# Wifi_Shield_v1_2.net
KiCad netlist of a schematic drawn in EAGLE
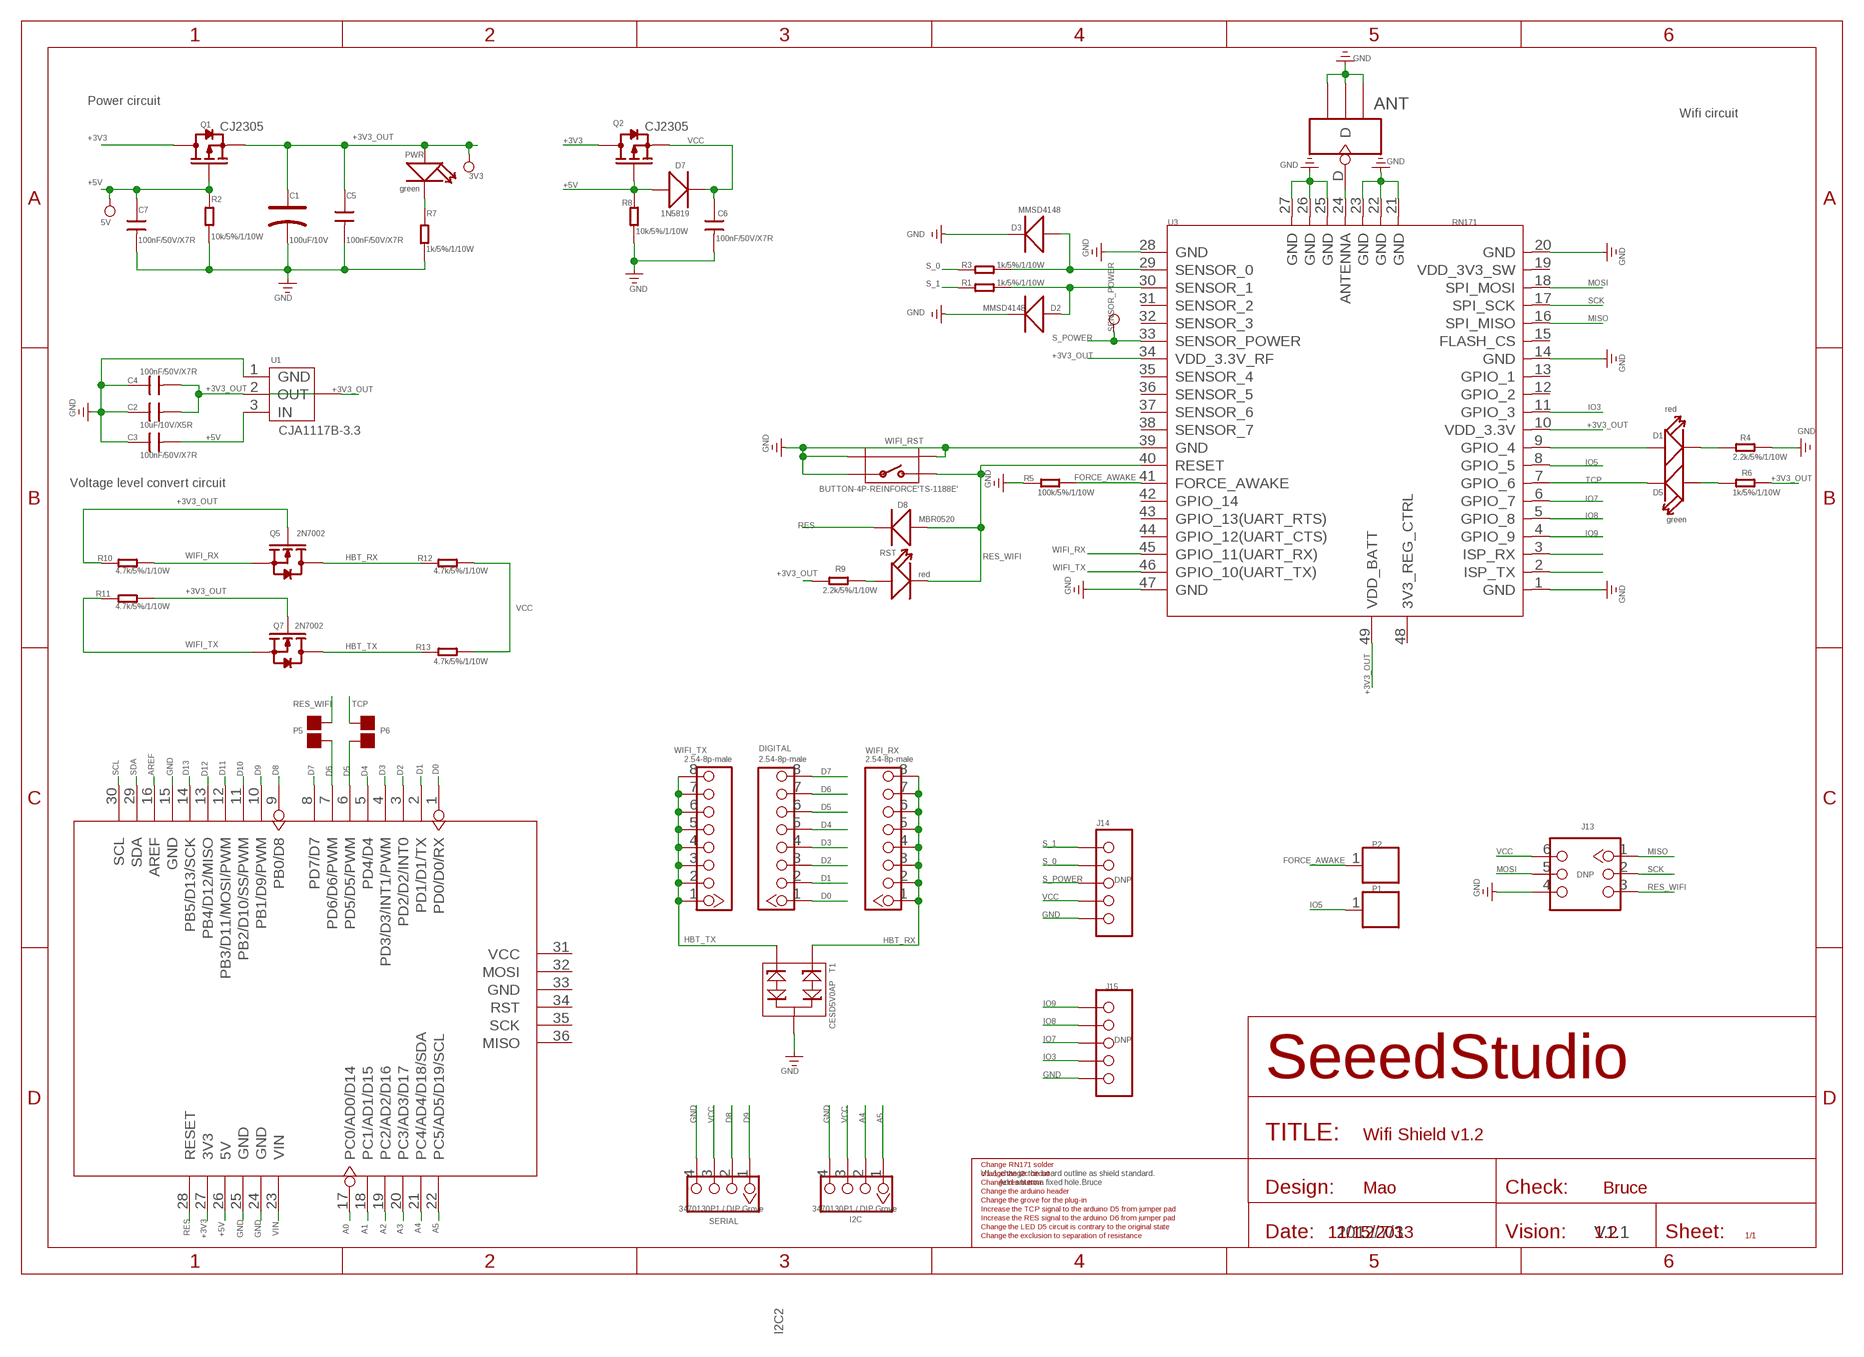
[diagram p0: schematic, sheet 1]

(export (version "E")
  (design (tool "Eeschema 10.0.6"))
  (components
    (comp (ref "3V3")
      (value "PAD-TEST-POINT-CIRCLE_SIZE_3030")
      (footprint "eagle-import:TP_3535")
      (libsource (lib "eagle-import") (part "PAD-TEST-POINT-CIRCLE_SIZE_3030"))
    )
    (comp (ref "5V")
      (value "PAD-TEST-POINT-CIRCLE_SIZE_3030")
      (footprint "eagle-import:TP_3535")
      (libsource (lib "eagle-import") (part "PAD-TEST-POINT-CIRCLE_SIZE_3030"))
    )
    (comp (ref "ANT1")
      (value "ANT")
      (footprint "eagle-import:4P-U-FL")
      (libsource (lib "eagle-import") (part "ANTENNA-U-FL"))
    )
    (comp (ref "C1")
      (value "100uF/10V")
      (footprint "eagle-import:AVX-B")
      (libsource (lib "eagle-import") (part "CAP-AVX-B"))
    )
    (comp (ref "C2")
      (value "10uF/10V/X5R")
      (footprint "eagle-import:0603")
      (libsource (lib "eagle-import") (part "C-0603"))
    )
    (comp (ref "C3")
      (value "100nF/50V/X7R")
      (footprint "eagle-import:0603")
      (libsource (lib "eagle-import") (part "C-0603"))
    )
    (comp (ref "C4")
      (value "100nF/50V/X7R")
      (footprint "eagle-import:0603")
      (libsource (lib "eagle-import") (part "C-0603"))
    )
    (comp (ref "C5")
      (value "100nF/50V/X7R")
      (footprint "eagle-import:0603")
      (libsource (lib "eagle-import") (part "C-0603"))
    )
    (comp (ref "C6")
      (value "100nF/50V/X7R")
      (footprint "eagle-import:0603")
      (libsource (lib "eagle-import") (part "C-0603"))
    )
    (comp (ref "C7")
      (value "100nF/50V/X7R")
      (footprint "eagle-import:0603")
      (libsource (lib "eagle-import") (part "C-0603"))
    )
    (comp (ref "D1")
      (value "red")
      (footprint "eagle-import:LED-0603")
      (libsource (lib "eagle-import") (part "LED'0603'"))
    )
    (comp (ref "D2")
      (value "MMSD4148")
      (footprint "eagle-import:SOD123-2.7X1.6")
      (libsource (lib "eagle-import") (part "D-MBR0520LT1"))
    )
    (comp (ref "D3")
      (value "MMSD4148")
      (footprint "eagle-import:SOD123-2.7X1.6")
      (libsource (lib "eagle-import") (part "D-MBR0520LT1"))
    )
    (comp (ref "D5")
      (value "green")
      (footprint "eagle-import:LED-0603")
      (libsource (lib "eagle-import") (part "LED'0603'"))
    )
    (comp (ref "D7")
      (value "1N5819")
      (footprint "eagle-import:D2010")
      (libsource (lib "eagle-import") (part "D-SMA"))
    )
    (comp (ref "D8")
      (value "MBR0520")
      (footprint "eagle-import:SOD123-2.7X1.6")
      (libsource (lib "eagle-import") (part "D-MBR0520LT1"))
    )
    (comp (ref "DIGITAL")
      (value "2.54-8p-male")
      (footprint "eagle-import:8P-2.54")
      (libsource (lib "eagle-import") (part "HEADER-8P-2.54"))
    )
    (comp (ref "I2C")
      (value "3470130P1 / DIP Grove")
      (footprint "eagle-import:4P-2.0")
      (libsource (lib "eagle-import") (part "TWIG-4P-2.0-2.0"))
    )
    (comp (ref "J13")
      (value "DNP")
      (footprint "eagle-import:2X3P-2.54")
      (libsource (lib "eagle-import") (part "HEADER-2X3P-2.54"))
    )
    (comp (ref "J14")
      (value "DNP")
      (footprint "eagle-import:5P-2.54")
      (libsource (lib "eagle-import") (part "HEADER-5P-2.54"))
    )
    (comp (ref "J15")
      (value "DNP")
      (footprint "eagle-import:5P-2.54")
      (libsource (lib "eagle-import") (part "HEADER-5P-2.54"))
    )
    (comp (ref "P1")
      (value "DNP")
      (footprint "eagle-import:1P-65_35MIL")
      (libsource (lib "eagle-import") (part "PAD'60/30'"))
    )
    (comp (ref "P2")
      (value "DNP")
      (footprint "eagle-import:1P-65_35MIL")
      (libsource (lib "eagle-import") (part "PAD'60/30'"))
    )
    (comp (ref "P5")
      (value "DNP")
      (footprint "eagle-import:2P-SMD-1.78X1.27")
      (libsource (lib "eagle-import") (part "PAD-JUMPER-2P"))
    )
    (comp (ref "P6")
      (value "DNP")
      (footprint "eagle-import:2P-SMD-1.78X1.27")
      (libsource (lib "eagle-import") (part "PAD-JUMPER-2P"))
    )
    (comp (ref "PWR")
      (value "green")
      (footprint "eagle-import:LED-0603")
      (libsource (lib "eagle-import") (part "LED'0603'"))
    )
    (comp (ref "Q1")
      (value "CJ2305")
      (footprint "eagle-import:SOT23")
      (libsource (lib "eagle-import") (part "MOSFET-P'SI2323CDS/SI2305DS{lt}BR{gt}'"))
    )
    (comp (ref "Q2")
      (value "CJ2305")
      (footprint "eagle-import:SOT23")
      (libsource (lib "eagle-import") (part "MOSFET-P'SI2323CDS/SI2305DS{lt}BR{gt}'"))
    )
    (comp (ref "Q5")
      (value "2N7002")
      (footprint "eagle-import:SOT23")
      (libsource (lib "eagle-import") (part "MOSFET-N'SOT23'"))
    )
    (comp (ref "Q7")
      (value "2N7002")
      (footprint "eagle-import:SOT23")
      (libsource (lib "eagle-import") (part "MOSFET-N'SOT23'"))
    )
    (comp (ref "R1")
      (value "1k/5%/1/10W")
      (footprint "eagle-import:0603")
      (libsource (lib "eagle-import") (part "R-0603"))
    )
    (comp (ref "R2")
      (value "10k/5%/1/10W")
      (footprint "eagle-import:0603")
      (libsource (lib "eagle-import") (part "R-0603"))
    )
    (comp (ref "R3")
      (value "1k/5%/1/10W")
      (footprint "eagle-import:0603")
      (libsource (lib "eagle-import") (part "R-0603"))
    )
    (comp (ref "R4")
      (value "2.2k/5%/1/10W")
      (footprint "eagle-import:0603")
      (libsource (lib "eagle-import") (part "R-0603"))
    )
    (comp (ref "R5")
      (value "100k/5%/1/10W")
      (footprint "eagle-import:0603")
      (libsource (lib "eagle-import") (part "R-0603"))
    )
    (comp (ref "R6")
      (value "1k/5%/1/10W")
      (footprint "eagle-import:0603")
      (libsource (lib "eagle-import") (part "R-0603"))
    )
    (comp (ref "R7")
      (value "1k/5%/1/10W")
      (footprint "eagle-import:0603")
      (libsource (lib "eagle-import") (part "R-0603"))
    )
    (comp (ref "R8")
      (value "10k/5%/1/10W")
      (footprint "eagle-import:0603")
      (libsource (lib "eagle-import") (part "R-0603"))
    )
    (comp (ref "R9")
      (value "2.2k/5%/1/10W")
      (footprint "eagle-import:0603")
      (libsource (lib "eagle-import") (part "R-0603"))
    )
    (comp (ref "R10")
      (value "4.7k/5%/1/10W")
      (footprint "eagle-import:0603")
      (libsource (lib "eagle-import") (part "R-0603"))
    )
    (comp (ref "R11")
      (value "4.7k/5%/1/10W")
      (footprint "eagle-import:0603")
      (libsource (lib "eagle-import") (part "R-0603"))
    )
    (comp (ref "R12")
      (value "4.7k/5%/1/10W")
      (footprint "eagle-import:0603")
      (libsource (lib "eagle-import") (part "R-0603"))
    )
    (comp (ref "R13")
      (value "4.7k/5%/1/10W")
      (footprint "eagle-import:0603")
      (libsource (lib "eagle-import") (part "R-0603"))
    )
    (comp (ref "RST")
      (value "red")
      (footprint "eagle-import:LED-0603")
      (libsource (lib "eagle-import") (part "LED'0603'"))
    )
    (comp (ref "SENSOR_POWER")
      (value "PAD-TEST-POINT-CIRCLE_SIZE_3030")
      (footprint "eagle-import:TP_3535")
      (libsource (lib "eagle-import") (part "PAD-TEST-POINT-CIRCLE_SIZE_3030"))
    )
    (comp (ref "SERIAL")
      (value "3470130P1 / DIP Grove")
      (footprint "eagle-import:4P-2.0")
      (libsource (lib "eagle-import") (part "TWIG-4P-2.0-2.0"))
    )
    (comp (ref "T1")
      (value "CESD5V0AP")
      (footprint "eagle-import:SOT23")
      (libsource (lib "eagle-import") (part "D-ESD-PESDXL2BT"))
    )
    (comp (ref "U1")
      (value "CJA1117B-3.3")
      (footprint "eagle-import:SOT89")
      (libsource (lib "eagle-import") (part "LD1117SOT89"))
    )
    (comp (ref "U2")
      (value "ARDUINO'W/O-SILK'")
      (footprint "eagle-import:ARDUINO-W_O-SILK")
      (libsource (lib "eagle-import") (part "ARDUINO'W/O-SILK'"))
    )
    (comp (ref "U3")
      (value "RN171")
      (footprint "eagle-import:49P-1.27-26.67X17.78")
      (libsource (lib "eagle-import") (part "WIFI-RN-171"))
    )
    (comp (ref "WIFI_RST")
      (value "BUTTON-4P-REINFORCE'TS-1188E'")
      (footprint "eagle-import:4P-SMD-7X3.5X3.5H")
      (libsource (lib "eagle-import") (part "BUTTON-4P-REINFORCE'TS-1188E'"))
    )
    (comp (ref "WIFI_RX")
      (value "2.54-8p-male")
      (footprint "eagle-import:8P-2.54")
      (libsource (lib "eagle-import") (part "HEADER-8P-2.54"))
    )
    (comp (ref "WIFI_TX")
      (value "2.54-8p-male")
      (footprint "eagle-import:8P-2.54")
      (libsource (lib "eagle-import") (part "HEADER-8P-2.54"))
    )
  )
  (nets
    (net (code "1") (name "/+3V3") (class "Default")
      (node (ref "Q1") (pin "3") (pinfunction "D_3") (pintype "passive"))
      (node (ref "Q2") (pin "3") (pinfunction "D_3") (pintype "passive"))
      (node (ref "U2") (pin "27") (pinfunction "3V3_27") (pintype "bidirectional"))
    )
    (net (code "2") (name "/+3V3_OUT") (class "Default")
      (node (ref "3V3") (pin "T") (pinfunction "T_T") (pintype "bidirectional"))
      (node (ref "C1") (pin "+") (pinfunction "+_+") (pintype "passive"))
      (node (ref "C2") (pin "2") (pinfunction "2_2") (pintype "passive"))
      (node (ref "C4") (pin "2") (pinfunction "2_2") (pintype "passive"))
      (node (ref "C5") (pin "1") (pinfunction "1_1") (pintype "passive"))
      (node (ref "PWR") (pin "+") (pinfunction "+_+") (pintype "passive"))
      (node (ref "Q1") (pin "2") (pinfunction "S_2") (pintype "passive"))
      (node (ref "Q5") (pin "1") (pinfunction "G_1") (pintype "passive"))
      (node (ref "Q7") (pin "1") (pinfunction "G_1") (pintype "passive"))
      (node (ref "R10") (pin "2") (pinfunction "2_2") (pintype "passive"))
      (node (ref "R11") (pin "1") (pinfunction "1_1") (pintype "passive"))
      (node (ref "R6") (pin "1") (pinfunction "1_1") (pintype "passive"))
      (node (ref "R9") (pin "2") (pinfunction "2_2") (pintype "passive"))
      (node (ref "U1") (pin "2") (pinfunction "OUT_2") (pintype "bidirectional"))
      (node (ref "U1") (pin "4") (pinfunction "TAB_4") (pintype "bidirectional"))
      (node (ref "U3") (pin "10") (pinfunction "VDD_3.3V_10") (pintype "power_in"))
      (node (ref "U3") (pin "34") (pinfunction "VDD_3.3V_RF_34") (pintype "power_in"))
      (node (ref "U3") (pin "49") (pinfunction "VDD_BATT_49") (pintype "bidirectional"))
    )
    (net (code "3") (name "/+5V") (class "Default")
      (node (ref "5V") (pin "T") (pinfunction "T_T") (pintype "bidirectional"))
      (node (ref "C3") (pin "2") (pinfunction "2_2") (pintype "passive"))
      (node (ref "C7") (pin "1") (pinfunction "1_1") (pintype "passive"))
      (node (ref "D7") (pin "+") (pinfunction "+_+") (pintype "passive"))
      (node (ref "Q1") (pin "1") (pinfunction "G_1") (pintype "passive"))
      (node (ref "Q2") (pin "1") (pinfunction "G_1") (pintype "passive"))
      (node (ref "R2") (pin "1") (pinfunction "1_1") (pintype "passive"))
      (node (ref "R8") (pin "1") (pinfunction "1_1") (pintype "passive"))
      (node (ref "U1") (pin "3") (pinfunction "IN_3") (pintype "bidirectional"))
      (node (ref "U2") (pin "26") (pinfunction "5V_26") (pintype "bidirectional"))
    )
    (net (code "4") (name "/A0") (class "Default")
      (node (ref "U2") (pin "17") (pinfunction "PC0/AD0/D14_17") (pintype "bidirectional"))
    )
    (net (code "5") (name "/A1") (class "Default")
      (node (ref "U2") (pin "18") (pinfunction "PC1/AD1/D15_18") (pintype "bidirectional"))
    )
    (net (code "6") (name "/A2") (class "Default")
      (node (ref "U2") (pin "19") (pinfunction "PC2/AD2/D16_19") (pintype "bidirectional"))
    )
    (net (code "7") (name "/A3") (class "Default")
      (node (ref "U2") (pin "20") (pinfunction "PC3/AD3/D17_20") (pintype "bidirectional"))
    )
    (net (code "8") (name "/A4") (class "Default")
      (node (ref "I2C") (pin "2") (pinfunction "2_2") (pintype "bidirectional"))
      (node (ref "U2") (pin "21") (pinfunction "PC4/AD4/D18/SDA_21") (pintype "bidirectional"))
    )
    (net (code "9") (name "/A5") (class "Default")
      (node (ref "I2C") (pin "1") (pinfunction "1_1") (pintype "bidirectional"))
      (node (ref "U2") (pin "22") (pinfunction "PC5/AD5/D19/SCL_22") (pintype "bidirectional"))
    )
    (net (code "10") (name "/AREF") (class "Default")
      (node (ref "U2") (pin "16") (pinfunction "AREF_16") (pintype "bidirectional"))
    )
    (net (code "11") (name "/D0") (class "Default")
      (node (ref "DIGITAL") (pin "1") (pinfunction "1_1") (pintype "bidirectional"))
      (node (ref "U2") (pin "1") (pinfunction "PD0/D0/RX_1") (pintype "bidirectional"))
    )
    (net (code "12") (name "/D1") (class "Default")
      (node (ref "DIGITAL") (pin "2") (pinfunction "2_2") (pintype "bidirectional"))
      (node (ref "U2") (pin "2") (pinfunction "PD1/D1/TX_2") (pintype "bidirectional"))
    )
    (net (code "13") (name "/D2") (class "Default")
      (node (ref "DIGITAL") (pin "3") (pinfunction "3_3") (pintype "bidirectional"))
      (node (ref "U2") (pin "3") (pinfunction "PD2/D2/INT0_3") (pintype "bidirectional"))
    )
    (net (code "14") (name "/D3") (class "Default")
      (node (ref "DIGITAL") (pin "4") (pinfunction "4_4") (pintype "bidirectional"))
      (node (ref "U2") (pin "4") (pinfunction "PD3/D3/INT1/PWM_4") (pintype "bidirectional"))
    )
    (net (code "15") (name "/D4") (class "Default")
      (node (ref "DIGITAL") (pin "5") (pinfunction "5_5") (pintype "bidirectional"))
      (node (ref "U2") (pin "5") (pinfunction "PD4/D4_5") (pintype "bidirectional"))
    )
    (net (code "16") (name "/D5") (class "Default")
      (node (ref "DIGITAL") (pin "6") (pinfunction "6_6") (pintype "bidirectional"))
      (node (ref "P6") (pin "2") (pinfunction "2_2") (pintype "bidirectional"))
      (node (ref "U2") (pin "6") (pinfunction "PD5/D5/PWM_6") (pintype "bidirectional"))
    )
    (net (code "17") (name "/D6") (class "Default")
      (node (ref "DIGITAL") (pin "7") (pinfunction "7_7") (pintype "bidirectional"))
      (node (ref "P5") (pin "1") (pinfunction "1_1") (pintype "bidirectional"))
      (node (ref "U2") (pin "7") (pinfunction "PD6/D6/PWM_7") (pintype "bidirectional"))
    )
    (net (code "18") (name "/D7") (class "Default")
      (node (ref "DIGITAL") (pin "8") (pinfunction "8_8") (pintype "bidirectional"))
      (node (ref "U2") (pin "8") (pinfunction "PD7/D7_8") (pintype "bidirectional"))
    )
    (net (code "19") (name "/D8") (class "Default")
      (node (ref "SERIAL") (pin "2") (pinfunction "2_2") (pintype "bidirectional"))
      (node (ref "U2") (pin "9") (pinfunction "PB0/D8_9") (pintype "bidirectional"))
    )
    (net (code "20") (name "/D9") (class "Default")
      (node (ref "SERIAL") (pin "1") (pinfunction "1_1") (pintype "bidirectional"))
      (node (ref "U2") (pin "10") (pinfunction "PB1/D9/PWM_10") (pintype "bidirectional"))
    )
    (net (code "21") (name "/D10") (class "Default")
      (node (ref "U2") (pin "11") (pinfunction "PB2/D10/SS/PWM_11") (pintype "bidirectional"))
    )
    (net (code "22") (name "/D11") (class "Default")
      (node (ref "U2") (pin "12") (pinfunction "PB3/D11/MOSI/PWM_12") (pintype "bidirectional"))
    )
    (net (code "23") (name "/D12") (class "Default")
      (node (ref "U2") (pin "13") (pinfunction "PB4/D12/MISO_13") (pintype "bidirectional"))
    )
    (net (code "24") (name "/D13") (class "Default")
      (node (ref "U2") (pin "14") (pinfunction "PB5/D13/SCK_14") (pintype "bidirectional"))
    )
    (net (code "25") (name "/FORCE_AWAKE") (class "Default")
      (node (ref "P2") (pin "1") (pinfunction "P$1_1") (pintype "bidirectional"))
      (node (ref "R5") (pin "1") (pinfunction "1_1") (pintype "passive"))
      (node (ref "U3") (pin "41") (pinfunction "FORCE_AWAKE_41") (pintype "bidirectional"))
    )
    (net (code "26") (name "/HBT_RX") (class "Default")
      (node (ref "Q5") (pin "3") (pinfunction "D_3") (pintype "passive"))
      (node (ref "R12") (pin "2") (pinfunction "2_2") (pintype "passive"))
      (node (ref "T1") (pin "1") (pinfunction "1_1") (pintype "power_in"))
      (node (ref "WIFI_RX") (pin "1") (pinfunction "1_1") (pintype "bidirectional"))
      (node (ref "WIFI_RX") (pin "2") (pinfunction "2_2") (pintype "bidirectional"))
      (node (ref "WIFI_RX") (pin "3") (pinfunction "3_3") (pintype "bidirectional"))
      (node (ref "WIFI_RX") (pin "4") (pinfunction "4_4") (pintype "bidirectional"))
      (node (ref "WIFI_RX") (pin "5") (pinfunction "5_5") (pintype "bidirectional"))
      (node (ref "WIFI_RX") (pin "6") (pinfunction "6_6") (pintype "bidirectional"))
      (node (ref "WIFI_RX") (pin "7") (pinfunction "7_7") (pintype "bidirectional"))
      (node (ref "WIFI_RX") (pin "8") (pinfunction "8_8") (pintype "bidirectional"))
    )
    (net (code "27") (name "/HBT_TX") (class "Default")
      (node (ref "Q7") (pin "3") (pinfunction "D_3") (pintype "passive"))
      (node (ref "R13") (pin "2") (pinfunction "2_2") (pintype "passive"))
      (node (ref "T1") (pin "2") (pinfunction "2_2") (pintype "power_in"))
      (node (ref "WIFI_TX") (pin "1") (pinfunction "1_1") (pintype "bidirectional"))
      (node (ref "WIFI_TX") (pin "2") (pinfunction "2_2") (pintype "bidirectional"))
      (node (ref "WIFI_TX") (pin "3") (pinfunction "3_3") (pintype "bidirectional"))
      (node (ref "WIFI_TX") (pin "4") (pinfunction "4_4") (pintype "bidirectional"))
      (node (ref "WIFI_TX") (pin "5") (pinfunction "5_5") (pintype "bidirectional"))
      (node (ref "WIFI_TX") (pin "6") (pinfunction "6_6") (pintype "bidirectional"))
      (node (ref "WIFI_TX") (pin "7") (pinfunction "7_7") (pintype "bidirectional"))
      (node (ref "WIFI_TX") (pin "8") (pinfunction "8_8") (pintype "bidirectional"))
    )
    (net (code "28") (name "/IO3") (class "Default")
      (node (ref "J15") (pin "4") (pinfunction "4_4") (pintype "bidirectional"))
      (node (ref "U3") (pin "11") (pinfunction "GPIO_3_11") (pintype "bidirectional"))
    )
    (net (code "29") (name "/IO5") (class "Default")
      (node (ref "P1") (pin "1") (pinfunction "P$1_1") (pintype "bidirectional"))
      (node (ref "U3") (pin "8") (pinfunction "GPIO_5_8") (pintype "bidirectional"))
    )
    (net (code "30") (name "/IO7") (class "Default")
      (node (ref "J15") (pin "3") (pinfunction "3_3") (pintype "bidirectional"))
      (node (ref "U3") (pin "6") (pinfunction "GPIO_7_6") (pintype "bidirectional"))
    )
    (net (code "31") (name "/IO8") (class "Default")
      (node (ref "J15") (pin "2") (pinfunction "2_2") (pintype "bidirectional"))
      (node (ref "U3") (pin "5") (pinfunction "GPIO_8_5") (pintype "bidirectional"))
    )
    (net (code "32") (name "/IO9") (class "Default")
      (node (ref "J15") (pin "1") (pinfunction "1_1") (pintype "bidirectional"))
      (node (ref "U3") (pin "4") (pinfunction "GPIO_9_4") (pintype "bidirectional"))
    )
    (net (code "33") (name "/MISO") (class "Default")
      (node (ref "J13") (pin "1") (pinfunction "1_1") (pintype "bidirectional"))
      (node (ref "U3") (pin "16") (pinfunction "SPI_MISO_16") (pintype "bidirectional"))
    )
    (net (code "34") (name "/MOSI") (class "Default")
      (node (ref "J13") (pin "5") (pinfunction "5_5") (pintype "bidirectional"))
      (node (ref "U3") (pin "18") (pinfunction "SPI_MOSI_18") (pintype "bidirectional"))
    )
    (net (code "35") (name "/RES") (class "Default")
      (node (ref "D8") (pin "1") (pinfunction "-_1") (pintype "passive"))
      (node (ref "U2") (pin "28") (pinfunction "RESET_28") (pintype "bidirectional"))
    )
    (net (code "36") (name "/RES_WIFI") (class "Default")
      (node (ref "D8") (pin "2") (pinfunction "+_2") (pintype "passive"))
      (node (ref "J13") (pin "3") (pinfunction "3_3") (pintype "bidirectional"))
      (node (ref "P5") (pin "2") (pinfunction "2_2") (pintype "bidirectional"))
      (node (ref "RST") (pin "-") (pinfunction "-_-") (pintype "passive"))
      (node (ref "U3") (pin "40") (pinfunction "RESET_40") (pintype "input"))
      (node (ref "WIFI_RST") (pin "2") (pinfunction "2_2") (pintype "bidirectional"))
    )
    (net (code "37") (name "/SCK") (class "Default")
      (node (ref "J13") (pin "2") (pinfunction "2_2") (pintype "bidirectional"))
      (node (ref "U3") (pin "17") (pinfunction "SPI_SCK_17") (pintype "bidirectional"))
    )
    (net (code "38") (name "/SCL") (class "Default")
      (node (ref "U2") (pin "30") (pinfunction "SCL_30") (pintype "bidirectional"))
    )
    (net (code "39") (name "/SDA") (class "Default")
      (node (ref "U2") (pin "29") (pinfunction "SDA_29") (pintype "bidirectional"))
    )
    (net (code "40") (name "/S_0") (class "Default")
      (node (ref "J14") (pin "2") (pinfunction "2_2") (pintype "bidirectional"))
      (node (ref "R3") (pin "2") (pinfunction "2_2") (pintype "passive"))
    )
    (net (code "41") (name "/S_1") (class "Default")
      (node (ref "J14") (pin "1") (pinfunction "1_1") (pintype "bidirectional"))
      (node (ref "R1") (pin "2") (pinfunction "2_2") (pintype "passive"))
    )
    (net (code "42") (name "/S_POWER") (class "Default")
      (node (ref "J14") (pin "3") (pinfunction "3_3") (pintype "bidirectional"))
      (node (ref "SENSOR_POWER") (pin "T") (pinfunction "T_T") (pintype "bidirectional"))
      (node (ref "U3") (pin "33") (pinfunction "SENSOR_POWER_33") (pintype "output"))
    )
    (net (code "43") (name "/TCP") (class "Default")
      (node (ref "D5") (pin "-") (pinfunction "-_-") (pintype "passive"))
      (node (ref "P6") (pin "1") (pinfunction "1_1") (pintype "bidirectional"))
      (node (ref "U3") (pin "7") (pinfunction "GPIO_6_7") (pintype "bidirectional"))
    )
    (net (code "44") (name "/VCC") (class "Default")
      (node (ref "C6") (pin "1") (pinfunction "1_1") (pintype "passive"))
      (node (ref "D7") (pin "-") (pinfunction "-_-") (pintype "passive"))
      (node (ref "I2C") (pin "3") (pinfunction "3_3") (pintype "bidirectional"))
      (node (ref "J13") (pin "6") (pinfunction "6_6") (pintype "bidirectional"))
      (node (ref "J14") (pin "4") (pinfunction "4_4") (pintype "bidirectional"))
      (node (ref "Q2") (pin "2") (pinfunction "S_2") (pintype "passive"))
      (node (ref "R12") (pin "1") (pinfunction "1_1") (pintype "passive"))
      (node (ref "R13") (pin "1") (pinfunction "1_1") (pintype "passive"))
      (node (ref "SERIAL") (pin "3") (pinfunction "3_3") (pintype "bidirectional"))
    )
    (net (code "45") (name "/VIN") (class "Default")
      (node (ref "U2") (pin "23") (pinfunction "VIN_23") (pintype "bidirectional"))
    )
    (net (code "46") (name "/WIFI_RX") (class "Default")
      (node (ref "Q5") (pin "2") (pinfunction "S_2") (pintype "passive"))
      (node (ref "R10") (pin "1") (pinfunction "1_1") (pintype "passive"))
      (node (ref "U3") (pin "45") (pinfunction "GPIO_11(UART_RX)_45") (pintype "bidirectional"))
    )
    (net (code "47") (name "/WIFI_TX") (class "Default")
      (node (ref "Q7") (pin "2") (pinfunction "S_2") (pintype "passive"))
      (node (ref "R11") (pin "2") (pinfunction "2_2") (pintype "passive"))
      (node (ref "U3") (pin "46") (pinfunction "GPIO_10(UART_TX)_46") (pintype "bidirectional"))
    )
    (net (code "48") (name "GND") (class "Default")
      (node (ref "ANT1") (pin "GND1") (pinfunction "GND1_GND1") (pintype "bidirectional"))
      (node (ref "ANT1") (pin "GND2") (pinfunction "GND2_GND2") (pintype "bidirectional"))
      (node (ref "ANT1") (pin "GND3") (pinfunction "GND3_GND3") (pintype "bidirectional"))
      (node (ref "C1") (pin "-") (pinfunction "-_-") (pintype "passive"))
      (node (ref "C2") (pin "1") (pinfunction "1_1") (pintype "passive"))
      (node (ref "C3") (pin "1") (pinfunction "1_1") (pintype "passive"))
      (node (ref "C4") (pin "1") (pinfunction "1_1") (pintype "passive"))
      (node (ref "C5") (pin "2") (pinfunction "2_2") (pintype "passive"))
      (node (ref "C6") (pin "2") (pinfunction "2_2") (pintype "passive"))
      (node (ref "C7") (pin "2") (pinfunction "2_2") (pintype "passive"))
      (node (ref "D2") (pin "1") (pinfunction "-_1") (pintype "passive"))
      (node (ref "D3") (pin "1") (pinfunction "-_1") (pintype "passive"))
      (node (ref "I2C") (pin "4") (pinfunction "4_4") (pintype "bidirectional"))
      (node (ref "J13") (pin "4") (pinfunction "4_4") (pintype "bidirectional"))
      (node (ref "J14") (pin "5") (pinfunction "5_5") (pintype "bidirectional"))
      (node (ref "J15") (pin "5") (pinfunction "5_5") (pintype "bidirectional"))
      (node (ref "R2") (pin "2") (pinfunction "2_2") (pintype "passive"))
      (node (ref "R4") (pin "1") (pinfunction "1_1") (pintype "passive"))
      (node (ref "R5") (pin "2") (pinfunction "2_2") (pintype "passive"))
      (node (ref "R7") (pin "1") (pinfunction "1_1") (pintype "passive"))
      (node (ref "R8") (pin "2") (pinfunction "2_2") (pintype "passive"))
      (node (ref "SERIAL") (pin "4") (pinfunction "4_4") (pintype "bidirectional"))
      (node (ref "T1") (pin "3") (pinfunction "3_3") (pintype "bidirectional"))
      (node (ref "U1") (pin "1") (pinfunction "GND_1") (pintype "bidirectional"))
      (node (ref "U2") (pin "15") (pinfunction "GND_15") (pintype "bidirectional"))
      (node (ref "U2") (pin "24") (pinfunction "GND_24") (pintype "bidirectional"))
      (node (ref "U2") (pin "25") (pinfunction "GND_25") (pintype "bidirectional"))
      (node (ref "U3") (pin "1") (pinfunction "GND_1") (pintype "power_in"))
      (node (ref "U3") (pin "14") (pinfunction "GND_14") (pintype "power_in"))
      (node (ref "U3") (pin "20") (pinfunction "GND_20") (pintype "power_in"))
      (node (ref "U3") (pin "21") (pinfunction "GND_21") (pintype "power_in"))
      (node (ref "U3") (pin "22") (pinfunction "GND_22") (pintype "power_in"))
      (node (ref "U3") (pin "23") (pinfunction "GND_23") (pintype "power_in"))
      (node (ref "U3") (pin "25") (pinfunction "GND_25") (pintype "power_in"))
      (node (ref "U3") (pin "26") (pinfunction "GND_26") (pintype "power_in"))
      (node (ref "U3") (pin "27") (pinfunction "GND_27") (pintype "power_in"))
      (node (ref "U3") (pin "28") (pinfunction "GND_28") (pintype "power_in"))
      (node (ref "U3") (pin "39") (pinfunction "GND_39") (pintype "power_in"))
      (node (ref "U3") (pin "47") (pinfunction "GND_47") (pintype "power_in"))
      (node (ref "WIFI_RST") (pin "1") (pinfunction "1_1") (pintype "bidirectional"))
      (node (ref "WIFI_RST") (pin "S1") (pinfunction "S1_S1") (pintype "bidirectional"))
      (node (ref "WIFI_RST") (pin "S2") (pinfunction "S2_S2") (pintype "bidirectional"))
    )
    (net (code "49") (name "Net-(D1-Pad-)") (class "Default")
      (node (ref "D1") (pin "-") (pinfunction "-_-") (pintype "passive"))
      (node (ref "R4") (pin "2") (pinfunction "2_2") (pintype "passive"))
    )
    (net (code "50") (name "Net-(D2-+)") (class "Default")
      (node (ref "D2") (pin "2") (pinfunction "+_2") (pintype "passive"))
      (node (ref "R1") (pin "1") (pinfunction "1_1") (pintype "passive"))
      (node (ref "U3") (pin "30") (pinfunction "SENSOR_1_30") (pintype "input"))
    )
    (net (code "51") (name "Net-(D3-+)") (class "Default")
      (node (ref "D3") (pin "2") (pinfunction "+_2") (pintype "passive"))
      (node (ref "R3") (pin "1") (pinfunction "1_1") (pintype "passive"))
      (node (ref "U3") (pin "29") (pinfunction "SENSOR_0_29") (pintype "input"))
    )
    (net (code "52") (name "Net-(D5-Pad+)") (class "Default")
      (node (ref "D5") (pin "+") (pinfunction "+_+") (pintype "passive"))
      (node (ref "R6") (pin "2") (pinfunction "2_2") (pintype "passive"))
    )
    (net (code "53") (name "Net-(PWR-Pad-)") (class "Default")
      (node (ref "PWR") (pin "-") (pinfunction "-_-") (pintype "passive"))
      (node (ref "R7") (pin "2") (pinfunction "2_2") (pintype "passive"))
    )
    (net (code "54") (name "Net-(R9-Pad1)") (class "Default")
      (node (ref "R9") (pin "1") (pinfunction "1_1") (pintype "passive"))
      (node (ref "RST") (pin "+") (pinfunction "+_+") (pintype "passive"))
    )
    (net (code "55") (name "Net-(U3-ANTENNA)") (class "Default")
      (node (ref "ANT1") (pin "D") (pinfunction "D_D") (pintype "bidirectional"))
      (node (ref "U3") (pin "24") (pinfunction "ANTENNA_24") (pintype "bidirectional"))
    )
    (net (code "56") (name "Net-(U3-GPIO_4)") (class "Default")
      (node (ref "D1") (pin "+") (pinfunction "+_+") (pintype "passive"))
      (node (ref "U3") (pin "9") (pinfunction "GPIO_4_9") (pintype "bidirectional"))
    )
    (net (code "57") (name "unconnected-(U2-GND-Pad33)") (class "Default")
      (node (ref "U2") (pin "33") (pinfunction "GND_33") (pintype "bidirectional"))
    )
    (net (code "58") (name "unconnected-(U2-MISO-Pad36)") (class "Default")
      (node (ref "U2") (pin "36") (pinfunction "MISO_36") (pintype "bidirectional"))
    )
    (net (code "59") (name "unconnected-(U2-MOSI-Pad32)") (class "Default")
      (node (ref "U2") (pin "32") (pinfunction "MOSI_32") (pintype "bidirectional"))
    )
    (net (code "60") (name "unconnected-(U2-RST-Pad34)") (class "Default")
      (node (ref "U2") (pin "34") (pinfunction "RST_34") (pintype "bidirectional"))
    )
    (net (code "61") (name "unconnected-(U2-SCK-Pad35)") (class "Default")
      (node (ref "U2") (pin "35") (pinfunction "SCK_35") (pintype "bidirectional"))
    )
    (net (code "62") (name "unconnected-(U2-VCC-Pad31)") (class "Default")
      (node (ref "U2") (pin "31") (pinfunction "VCC_31") (pintype "bidirectional"))
    )
    (net (code "63") (name "unconnected-(U3-3V3_REG_CTRL-Pad48)") (class "Default")
      (node (ref "U3") (pin "48") (pinfunction "3V3_REG_CTRL_48") (pintype "input"))
    )
    (net (code "64") (name "unconnected-(U3-FLASH_CS-Pad15)") (class "Default")
      (node (ref "U3") (pin "15") (pinfunction "FLASH_CS_15") (pintype "bidirectional"))
    )
    (net (code "65") (name "unconnected-(U3-GPIO_1-Pad13)") (class "Default")
      (node (ref "U3") (pin "13") (pinfunction "GPIO_1_13") (pintype "bidirectional"))
    )
    (net (code "66") (name "unconnected-(U3-GPIO_2-Pad12)") (class "Default")
      (node (ref "U3") (pin "12") (pinfunction "GPIO_2_12") (pintype "bidirectional"))
    )
    (net (code "67") (name "unconnected-(U3-GPIO_12(UART_CTS)-Pad44)") (class "Default")
      (node (ref "U3") (pin "44") (pinfunction "GPIO_12(UART_CTS)_44") (pintype "bidirectional"))
    )
    (net (code "68") (name "unconnected-(U3-GPIO_13(UART_RTS)-Pad43)") (class "Default")
      (node (ref "U3") (pin "43") (pinfunction "GPIO_13(UART_RTS)_43") (pintype "bidirectional"))
    )
    (net (code "69") (name "unconnected-(U3-GPIO_14-Pad42)") (class "Default")
      (node (ref "U3") (pin "42") (pinfunction "GPIO_14_42") (pintype "bidirectional"))
    )
    (net (code "70") (name "unconnected-(U3-ISP_RX-Pad3)") (class "Default")
      (node (ref "U3") (pin "3") (pinfunction "ISP_RX_3") (pintype "bidirectional"))
    )
    (net (code "71") (name "unconnected-(U3-ISP_TX-Pad2)") (class "Default")
      (node (ref "U3") (pin "2") (pinfunction "ISP_TX_2") (pintype "bidirectional"))
    )
    (net (code "72") (name "unconnected-(U3-SENSOR_2-Pad31)") (class "Default")
      (node (ref "U3") (pin "31") (pinfunction "SENSOR_2_31") (pintype "input"))
    )
    (net (code "73") (name "unconnected-(U3-SENSOR_3-Pad32)") (class "Default")
      (node (ref "U3") (pin "32") (pinfunction "SENSOR_3_32") (pintype "input"))
    )
    (net (code "74") (name "unconnected-(U3-SENSOR_4-Pad35)") (class "Default")
      (node (ref "U3") (pin "35") (pinfunction "SENSOR_4_35") (pintype "input"))
    )
    (net (code "75") (name "unconnected-(U3-SENSOR_5-Pad36)") (class "Default")
      (node (ref "U3") (pin "36") (pinfunction "SENSOR_5_36") (pintype "input"))
    )
    (net (code "76") (name "unconnected-(U3-SENSOR_6-Pad37)") (class "Default")
      (node (ref "U3") (pin "37") (pinfunction "SENSOR_6_37") (pintype "input"))
    )
    (net (code "77") (name "unconnected-(U3-SENSOR_7-Pad38)") (class "Default")
      (node (ref "U3") (pin "38") (pinfunction "SENSOR_7_38") (pintype "input"))
    )
    (net (code "78") (name "unconnected-(U3-VDD_3V3_SW-Pad19)") (class "Default")
      (node (ref "U3") (pin "19") (pinfunction "VDD_3V3_SW_19") (pintype "bidirectional"))
    )
  )
)
